# FMB-AB.net
KiCad netlist of a schematic drawn in Altium Designer
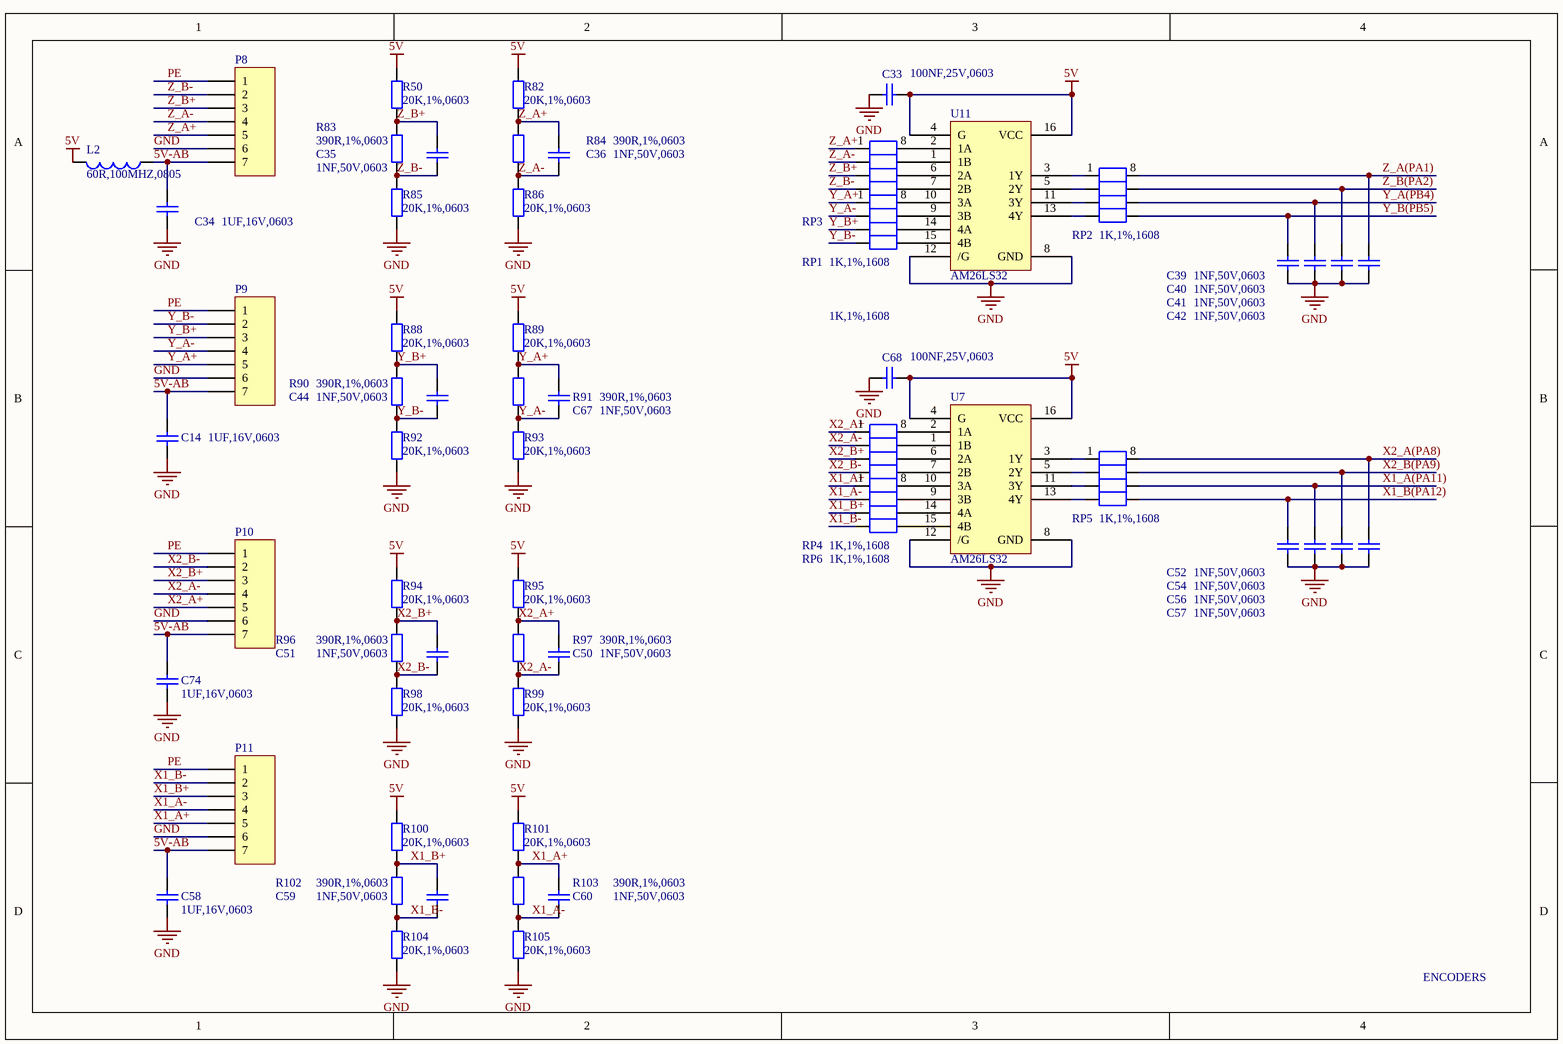
[diagram p0: FMB-AB.SchDoc]

(export (version "E")
  (design (tool "Eeschema 10.0.6"))
  (components
    (comp (ref "C14")
      (value "1UF,16V,0603")
      (footprint "RC0603")
      (description "Capacitor")
      (fields (field (name "PUBLISHER") "Altium Limited"))
      (libsource (lib "Miscellaneous Devices") (part "Cap"))
    )
    (comp (ref "C33")
      (value "100NF,25V,0603")
      (footprint "RC0603")
      (description "Capacitor")
      (fields (field (name "PUBLISHER") "Altium Limited"))
      (libsource (lib "Miscellaneous Devices") (part "Cap"))
    )
    (comp (ref "C34")
      (value "1UF,16V,0603")
      (footprint "RC0603")
      (description "Capacitor")
      (fields (field (name "PUBLISHER") "Altium Limited"))
      (libsource (lib "Miscellaneous Devices") (part "Cap"))
    )
    (comp (ref "C35")
      (value "1NF,50V,0603")
      (footprint "RC0603")
      (description "Capacitor")
      (fields (field (name "PUBLISHER") "Altium Limited"))
      (libsource (lib "Miscellaneous Devices") (part "Cap"))
    )
    (comp (ref "C36")
      (value "1NF,50V,0603")
      (footprint "RC0603")
      (description "Capacitor")
      (fields (field (name "PUBLISHER") "Altium Limited"))
      (libsource (lib "Miscellaneous Devices") (part "Cap"))
    )
    (comp (ref "C39")
      (value "1NF,50V,0603")
      (footprint "RC0603")
      (description "Capacitor")
      (fields (field (name "PUBLISHER") "Altium Limited"))
      (libsource (lib "Miscellaneous Devices") (part "Cap"))
    )
    (comp (ref "C40")
      (value "1NF,50V,0603")
      (footprint "RC0603")
      (description "Capacitor")
      (fields (field (name "PUBLISHER") "Altium Limited"))
      (libsource (lib "Miscellaneous Devices") (part "Cap"))
    )
    (comp (ref "C41")
      (value "1NF,50V,0603")
      (footprint "RC0603")
      (description "Capacitor")
      (fields (field (name "PUBLISHER") "Altium Limited"))
      (libsource (lib "Miscellaneous Devices") (part "Cap"))
    )
    (comp (ref "C42")
      (value "1NF,50V,0603")
      (footprint "RC0603")
      (description "Capacitor")
      (fields (field (name "PUBLISHER") "Altium Limited"))
      (libsource (lib "Miscellaneous Devices") (part "Cap"))
    )
    (comp (ref "C44")
      (value "1NF,50V,0603")
      (footprint "RC0603")
      (description "Capacitor")
      (fields (field (name "PUBLISHER") "Altium Limited"))
      (libsource (lib "Miscellaneous Devices") (part "Cap"))
    )
    (comp (ref "C50")
      (value "1NF,50V,0603")
      (footprint "RC0603")
      (description "Capacitor")
      (fields (field (name "PUBLISHER") "Altium Limited"))
      (libsource (lib "Miscellaneous Devices") (part "Cap"))
    )
    (comp (ref "C51")
      (value "1NF,50V,0603")
      (footprint "RC0603")
      (description "Capacitor")
      (fields (field (name "PUBLISHER") "Altium Limited"))
      (libsource (lib "Miscellaneous Devices") (part "Cap"))
    )
    (comp (ref "C52")
      (value "1NF,50V,0603")
      (footprint "RC0603")
      (description "Capacitor")
      (fields (field (name "PUBLISHER") "Altium Limited"))
      (libsource (lib "Miscellaneous Devices") (part "Cap"))
    )
    (comp (ref "C54")
      (value "1NF,50V,0603")
      (footprint "RC0603")
      (description "Capacitor")
      (fields (field (name "PUBLISHER") "Altium Limited"))
      (libsource (lib "Miscellaneous Devices") (part "Cap"))
    )
    (comp (ref "C56")
      (value "1NF,50V,0603")
      (footprint "RC0603")
      (description "Capacitor")
      (fields (field (name "PUBLISHER") "Altium Limited"))
      (libsource (lib "Miscellaneous Devices") (part "Cap"))
    )
    (comp (ref "C57")
      (value "1NF,50V,0603")
      (footprint "RC0603")
      (description "Capacitor")
      (fields (field (name "PUBLISHER") "Altium Limited"))
      (libsource (lib "Miscellaneous Devices") (part "Cap"))
    )
    (comp (ref "C58")
      (value "1UF,16V,0603")
      (footprint "RC0603")
      (description "Capacitor")
      (fields (field (name "PUBLISHER") "Altium Limited"))
      (libsource (lib "Miscellaneous Devices") (part "Cap"))
    )
    (comp (ref "C59")
      (value "1NF,50V,0603")
      (footprint "RC0603")
      (description "Capacitor")
      (fields (field (name "PUBLISHER") "Altium Limited"))
      (libsource (lib "Miscellaneous Devices") (part "Cap"))
    )
    (comp (ref "C60")
      (value "1NF,50V,0603")
      (footprint "RC0603")
      (description "Capacitor")
      (fields (field (name "PUBLISHER") "Altium Limited"))
      (libsource (lib "Miscellaneous Devices") (part "Cap"))
    )
    (comp (ref "C67")
      (value "1NF,50V,0603")
      (footprint "RC0603")
      (description "Capacitor")
      (fields (field (name "PUBLISHER") "Altium Limited"))
      (libsource (lib "Miscellaneous Devices") (part "Cap"))
    )
    (comp (ref "C68")
      (value "100NF,25V,0603")
      (footprint "RC0603")
      (description "Capacitor")
      (fields (field (name "PUBLISHER") "Altium Limited"))
      (libsource (lib "Miscellaneous Devices") (part "Cap"))
    )
    (comp (ref "C74")
      (value "1UF,16V,0603")
      (footprint "RC0603")
      (description "Capacitor")
      (fields (field (name "PUBLISHER") "Altium Limited"))
      (libsource (lib "Miscellaneous Devices") (part "Cap"))
    )
    (comp (ref "L2")
      (value "60R,100MHZ,0805")
      (footprint "RC0805")
      (description "Inductor")
      (fields (field (name "PUBLISHER") "Altium Limited"))
      (libsource (lib "Miscellaneous Devices") (part "Inductor"))
    )
    (comp (ref "P8")
      (value "Header 7")
      (footprint "DIP-1*7-2.54")
      (description "Header, 7-Pin")
      (fields (field (name "PUBLISHER") "Altium Limited"))
      (libsource (lib "Miscellaneous Connectors") (part "Header 7"))
    )
    (comp (ref "P9")
      (value "Header 7")
      (footprint "DIP-1*7-2.54")
      (description "Header, 7-Pin")
      (fields (field (name "PUBLISHER") "Altium Limited"))
      (libsource (lib "Miscellaneous Connectors") (part "Header 7"))
    )
    (comp (ref "P10")
      (value "Header 7")
      (footprint "DIP-1*7-2.54")
      (description "Header, 7-Pin")
      (fields (field (name "PUBLISHER") "Altium Limited"))
      (libsource (lib "Miscellaneous Connectors") (part "Header 7"))
    )
    (comp (ref "P11")
      (value "Header 7")
      (footprint "DIP-1*7-2.54")
      (description "Header, 7-Pin")
      (fields (field (name "PUBLISHER") "Altium Limited"))
      (libsource (lib "Miscellaneous Connectors") (part "Header 7"))
    )
    (comp (ref "R50")
      (value "20K,1%,0603")
      (footprint "RC0603")
      (description "Resistor")
      (fields (field (name "PUBLISHER") "Altium Limited"))
      (libsource (lib "Miscellaneous Devices") (part "Res2"))
    )
    (comp (ref "R82")
      (value "20K,1%,0603")
      (footprint "RC0603")
      (description "Resistor")
      (fields (field (name "PUBLISHER") "Altium Limited"))
      (libsource (lib "Miscellaneous Devices") (part "Res2"))
    )
    (comp (ref "R83")
      (value "390R,1%,0603")
      (footprint "RC0603")
      (description "Resistor")
      (fields (field (name "PUBLISHER") "Altium Limited"))
      (libsource (lib "Miscellaneous Devices") (part "Res2"))
    )
    (comp (ref "R84")
      (value "390R,1%,0603")
      (footprint "RC0603")
      (description "Resistor")
      (fields (field (name "PUBLISHER") "Altium Limited"))
      (libsource (lib "Miscellaneous Devices") (part "Res2"))
    )
    (comp (ref "R85")
      (value "20K,1%,0603")
      (footprint "RC0603")
      (description "Resistor")
      (fields (field (name "PUBLISHER") "Altium Limited"))
      (libsource (lib "Miscellaneous Devices") (part "Res2"))
    )
    (comp (ref "R86")
      (value "20K,1%,0603")
      (footprint "RC0603")
      (description "Resistor")
      (fields (field (name "PUBLISHER") "Altium Limited"))
      (libsource (lib "Miscellaneous Devices") (part "Res2"))
    )
    (comp (ref "R88")
      (value "20K,1%,0603")
      (footprint "RC0603")
      (description "Resistor")
      (fields (field (name "PUBLISHER") "Altium Limited"))
      (libsource (lib "Miscellaneous Devices") (part "Res2"))
    )
    (comp (ref "R89")
      (value "20K,1%,0603")
      (footprint "RC0603")
      (description "Resistor")
      (fields (field (name "PUBLISHER") "Altium Limited"))
      (libsource (lib "Miscellaneous Devices") (part "Res2"))
    )
    (comp (ref "R90")
      (value "390R,1%,0603")
      (footprint "RC0603")
      (description "Resistor")
      (fields (field (name "PUBLISHER") "Altium Limited"))
      (libsource (lib "Miscellaneous Devices") (part "Res2"))
    )
    (comp (ref "R91")
      (value "390R,1%,0603")
      (footprint "RC0603")
      (description "Resistor")
      (fields (field (name "PUBLISHER") "Altium Limited"))
      (libsource (lib "Miscellaneous Devices") (part "Res2"))
    )
    (comp (ref "R92")
      (value "20K,1%,0603")
      (footprint "RC0603")
      (description "Resistor")
      (fields (field (name "PUBLISHER") "Altium Limited"))
      (libsource (lib "Miscellaneous Devices") (part "Res2"))
    )
    (comp (ref "R93")
      (value "20K,1%,0603")
      (footprint "RC0603")
      (description "Resistor")
      (fields (field (name "PUBLISHER") "Altium Limited"))
      (libsource (lib "Miscellaneous Devices") (part "Res2"))
    )
    (comp (ref "R94")
      (value "20K,1%,0603")
      (footprint "RC0603")
      (description "Resistor")
      (fields (field (name "PUBLISHER") "Altium Limited"))
      (libsource (lib "Miscellaneous Devices") (part "Res2"))
    )
    (comp (ref "R95")
      (value "20K,1%,0603")
      (footprint "RC0603")
      (description "Resistor")
      (fields (field (name "PUBLISHER") "Altium Limited"))
      (libsource (lib "Miscellaneous Devices") (part "Res2"))
    )
    (comp (ref "R96")
      (value "390R,1%,0603")
      (footprint "RC0603")
      (description "Resistor")
      (fields (field (name "PUBLISHER") "Altium Limited"))
      (libsource (lib "Miscellaneous Devices") (part "Res2"))
    )
    (comp (ref "R97")
      (value "390R,1%,0603")
      (footprint "RC0603")
      (description "Resistor")
      (fields (field (name "PUBLISHER") "Altium Limited"))
      (libsource (lib "Miscellaneous Devices") (part "Res2"))
    )
    (comp (ref "R98")
      (value "20K,1%,0603")
      (footprint "RC0603")
      (description "Resistor")
      (fields (field (name "PUBLISHER") "Altium Limited"))
      (libsource (lib "Miscellaneous Devices") (part "Res2"))
    )
    (comp (ref "R99")
      (value "20K,1%,0603")
      (footprint "RC0603")
      (description "Resistor")
      (fields (field (name "PUBLISHER") "Altium Limited"))
      (libsource (lib "Miscellaneous Devices") (part "Res2"))
    )
    (comp (ref "R100")
      (value "20K,1%,0603")
      (footprint "RC0603")
      (description "Resistor")
      (fields (field (name "PUBLISHER") "Altium Limited"))
      (libsource (lib "Miscellaneous Devices") (part "Res2"))
    )
    (comp (ref "R101")
      (value "20K,1%,0603")
      (footprint "RC0603")
      (description "Resistor")
      (fields (field (name "PUBLISHER") "Altium Limited"))
      (libsource (lib "Miscellaneous Devices") (part "Res2"))
    )
    (comp (ref "R102")
      (value "390R,1%,0603")
      (footprint "RC0603")
      (description "Resistor")
      (fields (field (name "PUBLISHER") "Altium Limited"))
      (libsource (lib "Miscellaneous Devices") (part "Res2"))
    )
    (comp (ref "R103")
      (value "390R,1%,0603")
      (footprint "RC0603")
      (description "Resistor")
      (fields (field (name "PUBLISHER") "Altium Limited"))
      (libsource (lib "Miscellaneous Devices") (part "Res2"))
    )
    (comp (ref "R104")
      (value "20K,1%,0603")
      (footprint "RC0603")
      (description "Resistor")
      (fields (field (name "PUBLISHER") "Altium Limited"))
      (libsource (lib "Miscellaneous Devices") (part "Res2"))
    )
    (comp (ref "R105")
      (value "20K,1%,0603")
      (footprint "RC0603")
      (description "Resistor")
      (fields (field (name "PUBLISHER") "Altium Limited"))
      (libsource (lib "Miscellaneous Devices") (part "Res2"))
    )
    (comp (ref "RP1") (value "1K,1%,1608") (footprint "RP1608") (libsource (lib "LDO原理图库") (part "RP1608-1")))
    (comp (ref "RP2") (value "1K,1%,1608") (footprint "RP1608") (libsource (lib "LDO原理图库") (part "RP1608-1")))
    (comp (ref "RP3") (value "1K,1%,1608") (footprint "RP1608") (libsource (lib "LDO原理图库") (part "RP1608-1")))
    (comp (ref "RP4") (value "1K,1%,1608") (footprint "RP1608") (libsource (lib "LDO原理图库") (part "RP1608-1")))
    (comp (ref "RP5") (value "1K,1%,1608") (footprint "RP1608") (libsource (lib "LDO原理图库") (part "RP1608-1")))
    (comp (ref "RP6") (value "1K,1%,1608") (footprint "RP1608") (libsource (lib "LDO原理图库") (part "RP1608-1")))
    (comp (ref "U7") (value "AM26LS32") (footprint "SO-16-H") (libsource (lib "LDO原理图库") (part "AM26LS32")))
    (comp (ref "U11") (value "AM26LS32") (footprint "SO-16-H") (libsource (lib "LDO原理图库") (part "AM26LS32")))
  )
  (nets
    (net (code "1") (name "/5V-AB") (class "Default")
      (node (ref "C14") (pin "1") (pinfunction "1_1") (pintype "passive"))
      (node (ref "C34") (pin "1") (pinfunction "1_1") (pintype "passive"))
      (node (ref "C58") (pin "1") (pinfunction "1_1") (pintype "passive"))
      (node (ref "C74") (pin "1") (pinfunction "1_1") (pintype "passive"))
      (node (ref "L2") (pin "1") (pinfunction "1_1") (pintype "passive"))
      (node (ref "P10") (pin "7") (pinfunction "7_7") (pintype "passive"))
      (node (ref "P11") (pin "7") (pinfunction "7_7") (pintype "passive"))
      (node (ref "P8") (pin "7") (pinfunction "7_7") (pintype "passive"))
      (node (ref "P9") (pin "7") (pinfunction "7_7") (pintype "passive"))
    )
    (net (code "2") (name "/PE") (class "Default")
      (node (ref "P10") (pin "1") (pinfunction "1_1") (pintype "passive"))
      (node (ref "P11") (pin "1") (pinfunction "1_1") (pintype "passive"))
      (node (ref "P8") (pin "1") (pinfunction "1_1") (pintype "passive"))
      (node (ref "P9") (pin "1") (pinfunction "1_1") (pintype "passive"))
    )
    (net (code "3") (name "/X1_A(PA11)") (class "Default")
      (node (ref "C52") (pin "2") (pinfunction "2_2") (pintype "passive"))
      (node (ref "RP5") (pin "6") (pintype "passive"))
    )
    (net (code "4") (name "/X1_A+") (class "Default")
      (node (ref "C60") (pin "2") (pinfunction "2_2") (pintype "passive"))
      (node (ref "P11") (pin "5") (pinfunction "5_5") (pintype "passive"))
      (node (ref "R101") (pin "2") (pinfunction "2_2") (pintype "passive"))
      (node (ref "R103") (pin "1") (pinfunction "1_1") (pintype "passive"))
      (node (ref "RP6") (pin "1") (pintype "passive"))
    )
    (net (code "5") (name "/X1_A-") (class "Default")
      (node (ref "C60") (pin "1") (pinfunction "1_1") (pintype "passive"))
      (node (ref "P11") (pin "4") (pinfunction "4_4") (pintype "passive"))
      (node (ref "R103") (pin "2") (pinfunction "2_2") (pintype "passive"))
      (node (ref "R105") (pin "1") (pinfunction "1_1") (pintype "passive"))
      (node (ref "RP6") (pin "2") (pintype "passive"))
    )
    (net (code "6") (name "/X1_B(PA12)") (class "Default")
      (node (ref "C54") (pin "2") (pinfunction "2_2") (pintype "passive"))
      (node (ref "RP5") (pin "5") (pintype "passive"))
    )
    (net (code "7") (name "/X1_B+") (class "Default")
      (node (ref "C59") (pin "2") (pinfunction "2_2") (pintype "passive"))
      (node (ref "P11") (pin "3") (pinfunction "3_3") (pintype "passive"))
      (node (ref "R100") (pin "2") (pinfunction "2_2") (pintype "passive"))
      (node (ref "R102") (pin "1") (pinfunction "1_1") (pintype "passive"))
      (node (ref "RP6") (pin "3") (pintype "passive"))
    )
    (net (code "8") (name "/X1_B-") (class "Default")
      (node (ref "C59") (pin "1") (pinfunction "1_1") (pintype "passive"))
      (node (ref "P11") (pin "2") (pinfunction "2_2") (pintype "passive"))
      (node (ref "R102") (pin "2") (pinfunction "2_2") (pintype "passive"))
      (node (ref "R104") (pin "1") (pinfunction "1_1") (pintype "passive"))
      (node (ref "RP6") (pin "4") (pintype "passive"))
    )
    (net (code "9") (name "/X2_A(PA8)") (class "Default")
      (node (ref "C57") (pin "2") (pinfunction "2_2") (pintype "passive"))
      (node (ref "RP5") (pin "8") (pintype "passive"))
    )
    (net (code "10") (name "/X2_A+") (class "Default")
      (node (ref "C50") (pin "2") (pinfunction "2_2") (pintype "passive"))
      (node (ref "P10") (pin "5") (pinfunction "5_5") (pintype "passive"))
      (node (ref "R95") (pin "2") (pinfunction "2_2") (pintype "passive"))
      (node (ref "R97") (pin "1") (pinfunction "1_1") (pintype "passive"))
      (node (ref "RP4") (pin "1") (pintype "passive"))
    )
    (net (code "11") (name "/X2_A-") (class "Default")
      (node (ref "C50") (pin "1") (pinfunction "1_1") (pintype "passive"))
      (node (ref "P10") (pin "4") (pinfunction "4_4") (pintype "passive"))
      (node (ref "R97") (pin "2") (pinfunction "2_2") (pintype "passive"))
      (node (ref "R99") (pin "1") (pinfunction "1_1") (pintype "passive"))
      (node (ref "RP4") (pin "2") (pintype "passive"))
    )
    (net (code "12") (name "/X2_B(PA9)") (class "Default")
      (node (ref "C56") (pin "2") (pinfunction "2_2") (pintype "passive"))
      (node (ref "RP5") (pin "7") (pintype "passive"))
    )
    (net (code "13") (name "/X2_B+") (class "Default")
      (node (ref "C51") (pin "2") (pinfunction "2_2") (pintype "passive"))
      (node (ref "P10") (pin "3") (pinfunction "3_3") (pintype "passive"))
      (node (ref "R94") (pin "2") (pinfunction "2_2") (pintype "passive"))
      (node (ref "R96") (pin "1") (pinfunction "1_1") (pintype "passive"))
      (node (ref "RP4") (pin "3") (pintype "passive"))
    )
    (net (code "14") (name "/X2_B-") (class "Default")
      (node (ref "C51") (pin "1") (pinfunction "1_1") (pintype "passive"))
      (node (ref "P10") (pin "2") (pinfunction "2_2") (pintype "passive"))
      (node (ref "R96") (pin "2") (pinfunction "2_2") (pintype "passive"))
      (node (ref "R98") (pin "1") (pinfunction "1_1") (pintype "passive"))
      (node (ref "RP4") (pin "4") (pintype "passive"))
    )
    (net (code "15") (name "/Y_A(PB4)") (class "Default")
      (node (ref "C39") (pin "2") (pinfunction "2_2") (pintype "passive"))
      (node (ref "RP2") (pin "6") (pintype "passive"))
    )
    (net (code "16") (name "/Y_A+") (class "Default")
      (node (ref "C67") (pin "2") (pinfunction "2_2") (pintype "passive"))
      (node (ref "P9") (pin "5") (pinfunction "5_5") (pintype "passive"))
      (node (ref "R89") (pin "2") (pinfunction "2_2") (pintype "passive"))
      (node (ref "R91") (pin "1") (pinfunction "1_1") (pintype "passive"))
      (node (ref "RP3") (pin "1") (pintype "passive"))
    )
    (net (code "17") (name "/Y_A-") (class "Default")
      (node (ref "C67") (pin "1") (pinfunction "1_1") (pintype "passive"))
      (node (ref "P9") (pin "4") (pinfunction "4_4") (pintype "passive"))
      (node (ref "R91") (pin "2") (pinfunction "2_2") (pintype "passive"))
      (node (ref "R93") (pin "1") (pinfunction "1_1") (pintype "passive"))
      (node (ref "RP3") (pin "2") (pintype "passive"))
    )
    (net (code "18") (name "/Y_B(PB5)") (class "Default")
      (node (ref "C40") (pin "2") (pinfunction "2_2") (pintype "passive"))
      (node (ref "RP2") (pin "5") (pintype "passive"))
    )
    (net (code "19") (name "/Y_B+") (class "Default")
      (node (ref "C44") (pin "2") (pinfunction "2_2") (pintype "passive"))
      (node (ref "P9") (pin "3") (pinfunction "3_3") (pintype "passive"))
      (node (ref "R88") (pin "2") (pinfunction "2_2") (pintype "passive"))
      (node (ref "R90") (pin "1") (pinfunction "1_1") (pintype "passive"))
      (node (ref "RP3") (pin "3") (pintype "passive"))
    )
    (net (code "20") (name "/Y_B-") (class "Default")
      (node (ref "C44") (pin "1") (pinfunction "1_1") (pintype "passive"))
      (node (ref "P9") (pin "2") (pinfunction "2_2") (pintype "passive"))
      (node (ref "R90") (pin "2") (pinfunction "2_2") (pintype "passive"))
      (node (ref "R92") (pin "1") (pinfunction "1_1") (pintype "passive"))
      (node (ref "RP3") (pin "4") (pintype "passive"))
    )
    (net (code "21") (name "/Z_A(PA1)") (class "Default")
      (node (ref "C42") (pin "2") (pinfunction "2_2") (pintype "passive"))
      (node (ref "RP2") (pin "8") (pintype "passive"))
    )
    (net (code "22") (name "/Z_A+") (class "Default")
      (node (ref "C36") (pin "2") (pinfunction "2_2") (pintype "passive"))
      (node (ref "P8") (pin "5") (pinfunction "5_5") (pintype "passive"))
      (node (ref "R82") (pin "2") (pinfunction "2_2") (pintype "passive"))
      (node (ref "R84") (pin "1") (pinfunction "1_1") (pintype "passive"))
      (node (ref "RP1") (pin "1") (pintype "passive"))
    )
    (net (code "23") (name "/Z_A-") (class "Default")
      (node (ref "C36") (pin "1") (pinfunction "1_1") (pintype "passive"))
      (node (ref "P8") (pin "4") (pinfunction "4_4") (pintype "passive"))
      (node (ref "R84") (pin "2") (pinfunction "2_2") (pintype "passive"))
      (node (ref "R86") (pin "1") (pinfunction "1_1") (pintype "passive"))
      (node (ref "RP1") (pin "2") (pintype "passive"))
    )
    (net (code "24") (name "/Z_B(PA2)") (class "Default")
      (node (ref "C41") (pin "2") (pinfunction "2_2") (pintype "passive"))
      (node (ref "RP2") (pin "7") (pintype "passive"))
    )
    (net (code "25") (name "/Z_B+") (class "Default")
      (node (ref "C35") (pin "2") (pinfunction "2_2") (pintype "passive"))
      (node (ref "P8") (pin "3") (pinfunction "3_3") (pintype "passive"))
      (node (ref "R50") (pin "2") (pinfunction "2_2") (pintype "passive"))
      (node (ref "R83") (pin "1") (pinfunction "1_1") (pintype "passive"))
      (node (ref "RP1") (pin "3") (pintype "passive"))
    )
    (net (code "26") (name "/Z_B-") (class "Default")
      (node (ref "C35") (pin "1") (pinfunction "1_1") (pintype "passive"))
      (node (ref "P8") (pin "2") (pinfunction "2_2") (pintype "passive"))
      (node (ref "R83") (pin "2") (pinfunction "2_2") (pintype "passive"))
      (node (ref "R85") (pin "1") (pinfunction "1_1") (pintype "passive"))
      (node (ref "RP1") (pin "4") (pintype "passive"))
    )
    (net (code "27") (name "5V") (class "Default")
      (node (ref "C33") (pin "1") (pinfunction "1_1") (pintype "passive"))
      (node (ref "C68") (pin "1") (pinfunction "1_1") (pintype "passive"))
      (node (ref "L2") (pin "2") (pinfunction "2_2") (pintype "passive"))
      (node (ref "R100") (pin "1") (pinfunction "1_1") (pintype "passive"))
      (node (ref "R101") (pin "1") (pinfunction "1_1") (pintype "passive"))
      (node (ref "R50") (pin "1") (pinfunction "1_1") (pintype "passive"))
      (node (ref "R82") (pin "1") (pinfunction "1_1") (pintype "passive"))
      (node (ref "R88") (pin "1") (pinfunction "1_1") (pintype "passive"))
      (node (ref "R89") (pin "1") (pinfunction "1_1") (pintype "passive"))
      (node (ref "R94") (pin "1") (pinfunction "1_1") (pintype "passive"))
      (node (ref "R95") (pin "1") (pinfunction "1_1") (pintype "passive"))
      (node (ref "U11") (pin "16") (pinfunction "VCC_16") (pintype "passive"))
      (node (ref "U11") (pin "4") (pinfunction "G_4") (pintype "passive"))
      (node (ref "U7") (pin "16") (pinfunction "VCC_16") (pintype "passive"))
      (node (ref "U7") (pin "4") (pinfunction "G_4") (pintype "passive"))
    )
    (net (code "28") (name "GND") (class "Default")
      (node (ref "C14") (pin "2") (pinfunction "2_2") (pintype "passive"))
      (node (ref "C33") (pin "2") (pinfunction "2_2") (pintype "passive"))
      (node (ref "C34") (pin "2") (pinfunction "2_2") (pintype "passive"))
      (node (ref "C39") (pin "1") (pinfunction "1_1") (pintype "passive"))
      (node (ref "C40") (pin "1") (pinfunction "1_1") (pintype "passive"))
      (node (ref "C41") (pin "1") (pinfunction "1_1") (pintype "passive"))
      (node (ref "C42") (pin "1") (pinfunction "1_1") (pintype "passive"))
      (node (ref "C52") (pin "1") (pinfunction "1_1") (pintype "passive"))
      (node (ref "C54") (pin "1") (pinfunction "1_1") (pintype "passive"))
      (node (ref "C56") (pin "1") (pinfunction "1_1") (pintype "passive"))
      (node (ref "C57") (pin "1") (pinfunction "1_1") (pintype "passive"))
      (node (ref "C58") (pin "2") (pinfunction "2_2") (pintype "passive"))
      (node (ref "C68") (pin "2") (pinfunction "2_2") (pintype "passive"))
      (node (ref "C74") (pin "2") (pinfunction "2_2") (pintype "passive"))
      (node (ref "P10") (pin "6") (pinfunction "6_6") (pintype "passive"))
      (node (ref "P11") (pin "6") (pinfunction "6_6") (pintype "passive"))
      (node (ref "P8") (pin "6") (pinfunction "6_6") (pintype "passive"))
      (node (ref "P9") (pin "6") (pinfunction "6_6") (pintype "passive"))
      (node (ref "R104") (pin "2") (pinfunction "2_2") (pintype "passive"))
      (node (ref "R105") (pin "2") (pinfunction "2_2") (pintype "passive"))
      (node (ref "R85") (pin "2") (pinfunction "2_2") (pintype "passive"))
      (node (ref "R86") (pin "2") (pinfunction "2_2") (pintype "passive"))
      (node (ref "R92") (pin "2") (pinfunction "2_2") (pintype "passive"))
      (node (ref "R93") (pin "2") (pinfunction "2_2") (pintype "passive"))
      (node (ref "R98") (pin "2") (pinfunction "2_2") (pintype "passive"))
      (node (ref "R99") (pin "2") (pinfunction "2_2") (pintype "passive"))
      (node (ref "U11") (pin "12") (pinfunction "/G_12") (pintype "passive"))
      (node (ref "U11") (pin "8") (pinfunction "GND_8") (pintype "passive"))
      (node (ref "U7") (pin "12") (pinfunction "/G_12") (pintype "passive"))
      (node (ref "U7") (pin "8") (pinfunction "GND_8") (pintype "passive"))
    )
    (net (code "29") (name "Net-(U7-1A)") (class "Default")
      (node (ref "RP4") (pin "8") (pintype "passive"))
      (node (ref "U7") (pin "2") (pinfunction "1A_2") (pintype "passive"))
    )
    (net (code "30") (name "Net-(U7-1B)") (class "Default")
      (node (ref "RP4") (pin "7") (pintype "passive"))
      (node (ref "U7") (pin "1") (pinfunction "1B_1") (pintype "passive"))
    )
    (net (code "31") (name "Net-(U7-1Y)") (class "Default")
      (node (ref "RP5") (pin "1") (pintype "passive"))
      (node (ref "U7") (pin "3") (pinfunction "1Y_3") (pintype "passive"))
    )
    (net (code "32") (name "Net-(U7-2A)") (class "Default")
      (node (ref "RP4") (pin "6") (pintype "passive"))
      (node (ref "U7") (pin "6") (pinfunction "2A_6") (pintype "passive"))
    )
    (net (code "33") (name "Net-(U7-2B)") (class "Default")
      (node (ref "RP4") (pin "5") (pintype "passive"))
      (node (ref "U7") (pin "7") (pinfunction "2B_7") (pintype "passive"))
    )
    (net (code "34") (name "Net-(U7-2Y)") (class "Default")
      (node (ref "RP5") (pin "2") (pintype "passive"))
      (node (ref "U7") (pin "5") (pinfunction "2Y_5") (pintype "passive"))
    )
    (net (code "35") (name "Net-(U7-3A)") (class "Default")
      (node (ref "RP6") (pin "8") (pintype "passive"))
      (node (ref "U7") (pin "10") (pinfunction "3A_10") (pintype "passive"))
    )
    (net (code "36") (name "Net-(U7-3B)") (class "Default")
      (node (ref "RP6") (pin "7") (pintype "passive"))
      (node (ref "U7") (pin "9") (pinfunction "3B_9") (pintype "passive"))
    )
    (net (code "37") (name "Net-(U7-3Y)") (class "Default")
      (node (ref "RP5") (pin "3") (pintype "passive"))
      (node (ref "U7") (pin "11") (pinfunction "3Y_11") (pintype "passive"))
    )
    (net (code "38") (name "Net-(U7-4A)") (class "Default")
      (node (ref "RP6") (pin "6") (pintype "passive"))
      (node (ref "U7") (pin "14") (pinfunction "4A_14") (pintype "passive"))
    )
    (net (code "39") (name "Net-(U7-4B)") (class "Default")
      (node (ref "RP6") (pin "5") (pintype "passive"))
      (node (ref "U7") (pin "15") (pinfunction "4B_15") (pintype "passive"))
    )
    (net (code "40") (name "Net-(U7-4Y)") (class "Default")
      (node (ref "RP5") (pin "4") (pintype "passive"))
      (node (ref "U7") (pin "13") (pinfunction "4Y_13") (pintype "passive"))
    )
    (net (code "41") (name "Net-(U11-1A)") (class "Default")
      (node (ref "RP1") (pin "8") (pintype "passive"))
      (node (ref "U11") (pin "2") (pinfunction "1A_2") (pintype "passive"))
    )
    (net (code "42") (name "Net-(U11-1B)") (class "Default")
      (node (ref "RP1") (pin "7") (pintype "passive"))
      (node (ref "U11") (pin "1") (pinfunction "1B_1") (pintype "passive"))
    )
    (net (code "43") (name "Net-(U11-1Y)") (class "Default")
      (node (ref "RP2") (pin "1") (pintype "passive"))
      (node (ref "U11") (pin "3") (pinfunction "1Y_3") (pintype "passive"))
    )
    (net (code "44") (name "Net-(U11-2A)") (class "Default")
      (node (ref "RP1") (pin "6") (pintype "passive"))
      (node (ref "U11") (pin "6") (pinfunction "2A_6") (pintype "passive"))
    )
    (net (code "45") (name "Net-(U11-2B)") (class "Default")
      (node (ref "RP1") (pin "5") (pintype "passive"))
      (node (ref "U11") (pin "7") (pinfunction "2B_7") (pintype "passive"))
    )
    (net (code "46") (name "Net-(U11-2Y)") (class "Default")
      (node (ref "RP2") (pin "2") (pintype "passive"))
      (node (ref "U11") (pin "5") (pinfunction "2Y_5") (pintype "passive"))
    )
    (net (code "47") (name "Net-(U11-3A)") (class "Default")
      (node (ref "RP3") (pin "8") (pintype "passive"))
      (node (ref "U11") (pin "10") (pinfunction "3A_10") (pintype "passive"))
    )
    (net (code "48") (name "Net-(U11-3B)") (class "Default")
      (node (ref "RP3") (pin "7") (pintype "passive"))
      (node (ref "U11") (pin "9") (pinfunction "3B_9") (pintype "passive"))
    )
    (net (code "49") (name "Net-(U11-3Y)") (class "Default")
      (node (ref "RP2") (pin "3") (pintype "passive"))
      (node (ref "U11") (pin "11") (pinfunction "3Y_11") (pintype "passive"))
    )
    (net (code "50") (name "Net-(U11-4A)") (class "Default")
      (node (ref "RP3") (pin "6") (pintype "passive"))
      (node (ref "U11") (pin "14") (pinfunction "4A_14") (pintype "passive"))
    )
    (net (code "51") (name "Net-(U11-4B)") (class "Default")
      (node (ref "RP3") (pin "5") (pintype "passive"))
      (node (ref "U11") (pin "15") (pinfunction "4B_15") (pintype "passive"))
    )
    (net (code "52") (name "Net-(U11-4Y)") (class "Default")
      (node (ref "RP2") (pin "4") (pintype "passive"))
      (node (ref "U11") (pin "13") (pinfunction "4Y_13") (pintype "passive"))
    )
  )
)
